# Bike_Gps_v1.net
KiCad netlist of a schematic drawn in Altium Designer
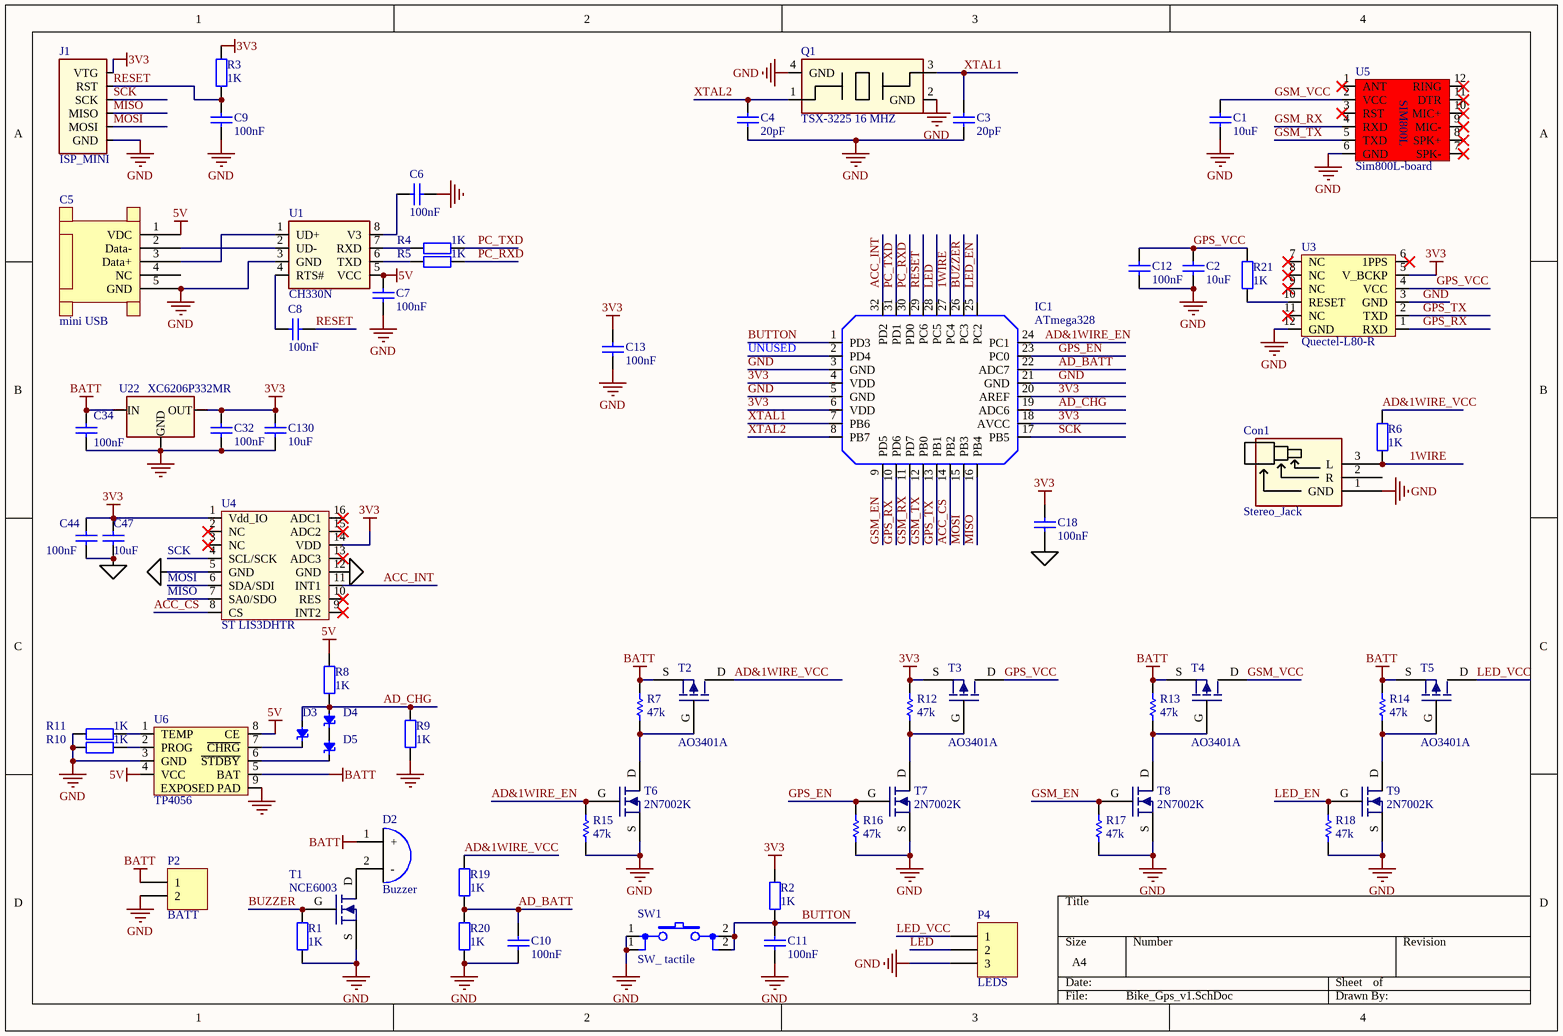
[diagram p0: Bike_Gps_v1.SchDoc]

(export (version "E")
  (design (tool "Eeschema 10.0.6"))
  (components
    (comp (ref "C1")
      (value "10uF")
      (footprint "FP_1206_CAP_085")
      (description "Capacitor ceramic X7R")
      (libsource (lib "Capacitor") (part "Cap"))
    )
    (comp (ref "C2")
      (value "10uF")
      (footprint "FP_1206_CAP_085")
      (description "Capacitor ceramic X7R")
      (libsource (lib "Capacitor") (part "Cap"))
    )
    (comp (ref "C3")
      (value "20pF")
      (footprint "FP_0603_CAP_080")
      (description "Capacitor")
      (fields (field (name "PART NUMBER") "20pF_0603_50V_NP0_5percent"))
      (libsource (lib "Miscellaneous Devices") (part "Cap"))
    )
    (comp (ref "C4")
      (value "20pF")
      (footprint "FP_0603_CAP_080")
      (description "Capacitor")
      (fields (field (name "PART NUMBER") "20pF_0603_50V_NP0_5percent"))
      (libsource (lib "Miscellaneous Devices") (part "Cap"))
    )
    (comp (ref "C5")
      (value "mini USB")
      (footprint "USB/SM0.8-6H5")
      (libsource (lib "mini USB") (part "mini USB"))
    )
    (comp (ref "C6")
      (value "100nF")
      (footprint "FP_0603_CAP_080")
      (description "Capacitor")
      (fields (field (name "PART NUMBER") "100nF_0603_50V_X7R_10percent"))
      (libsource (lib "Miscellaneous Devices") (part "Cap"))
    )
    (comp (ref "C7")
      (value "100nF")
      (footprint "FP_0603_CAP_080")
      (description "Capacitor")
      (fields (field (name "PART NUMBER") "100nF_0603_50V_X7R_10percent"))
      (libsource (lib "Miscellaneous Devices") (part "Cap"))
    )
    (comp (ref "C8")
      (value "100nF")
      (footprint "FP_0603_CAP_080")
      (description "Capacitor")
      (fields (field (name "PART NUMBER") "100nF_0603_50V_X7R_10percent"))
      (libsource (lib "Miscellaneous Devices") (part "Cap"))
    )
    (comp (ref "C9")
      (value "100nF")
      (footprint "FP_0603_CAP_080")
      (description "Capacitor")
      (fields (field (name "PART NUMBER") "100nF_0603_50V_X7R_10percent"))
      (libsource (lib "Miscellaneous Devices") (part "Cap"))
    )
    (comp (ref "C10")
      (value "100nF")
      (footprint "FP_0603_CAP_080")
      (description "Capacitor")
      (fields (field (name "PART NUMBER") "100nF_0603_50V_X7R_10percent"))
      (libsource (lib "Miscellaneous Devices") (part "Cap"))
    )
    (comp (ref "C11")
      (value "100nF")
      (footprint "FP_0603_CAP_080")
      (description "Capacitor")
      (fields (field (name "PART NUMBER") "100nF_0603_50V_X7R_10percent"))
      (libsource (lib "Miscellaneous Devices") (part "Cap"))
    )
    (comp (ref "C12")
      (value "100nF")
      (footprint "FP_0603_CAP_080")
      (description "Capacitor")
      (fields (field (name "PART NUMBER") "100nF_0603_50V_X7R_10percent"))
      (libsource (lib "Miscellaneous Devices") (part "Cap"))
    )
    (comp (ref "C13")
      (value "100nF")
      (footprint "FP_0603_CAP_080")
      (description "Capacitor")
      (fields (field (name "PART NUMBER") "100nF_0603_50V_X7R_10percent"))
      (libsource (lib "Miscellaneous Devices") (part "Cap"))
    )
    (comp (ref "C18")
      (value "100nF")
      (footprint "FP_0603_CAP_080")
      (description "Capacitor")
      (fields (field (name "PART NUMBER") "100nF_0603_50V_X7R_10percent"))
      (libsource (lib "Miscellaneous Devices") (part "Cap"))
    )
    (comp (ref "C32")
      (value "100nF")
      (footprint "FP_0603_CAP_080")
      (description "Capacitor")
      (fields (field (name "PART NUMBER") "100nF_0603_50V_X7R_10percent"))
      (libsource (lib "Miscellaneous Devices") (part "Cap"))
    )
    (comp (ref "C34")
      (value "100nF")
      (footprint "FP_0603_CAP_080")
      (description "Capacitor")
      (fields (field (name "PART NUMBER") "100nF_0603_50V_X7R_10percent"))
      (libsource (lib "Miscellaneous Devices") (part "Cap"))
    )
    (comp (ref "C44")
      (value "100nF")
      (footprint "FP_0603_CAP_080")
      (description "Capacitor")
      (fields (field (name "PART NUMBER") "100nF_0603_50V_X7R_10percent"))
      (libsource (lib "Capacitor") (part "CAP"))
    )
    (comp (ref "C47")
      (value "10uF")
      (footprint "FP_0805_CAP_085")
      (description "Capacitor")
      (fields (field (name "PART NUMBER") "10uF_0805_10V_X5R_10percent"))
      (libsource (lib "Capacitor") (part "CAP"))
    )
    (comp (ref "C130")
      (value "10uF")
      (footprint "FP_0805_CAP_085")
      (description "Capacitor")
      (fields (field (name "PART NUMBER") "10uF_0805_10V_X5R_10percent"))
      (libsource (lib "Capacitor") (part "CAP"))
    )
    (comp (ref "Con1")
      (value "Stereo_Jack")
      (footprint "STEREO_JACK")
      (libsource (lib "Connector") (part "Stereo_Jack"))
    )
    (comp (ref "D2") (value "Buzzer") (footprint "Buzzer_MBS12XXX") (libsource (lib "Other") (part "Buzzer")))
    (comp (ref "D3")
      (value "5.6V Zener")
      (footprint "FP_SOD323")
      (description "5.6V ±5% 300mW 1uA @ 2.5V SOD-323 Zener Diodes RoHS")
      (fields (field (name "PART NUMBER") "MM3Z5V6"))
      (libsource (lib "Diode") (part "5.6V Zener"))
    )
    (comp (ref "D4")
      (value "5.6V Zener")
      (footprint "FP_SOD323")
      (description "5.6V ±5% 300mW 1uA @ 2.5V SOD-323 Zener Diodes RoHS")
      (fields (field (name "PART NUMBER") "MM3Z5V6"))
      (libsource (lib "Diode") (part "5.6V Zener"))
    )
    (comp (ref "D5")
      (value "5.6V Zener")
      (footprint "FP_SOD323")
      (description "5.6V ±5% 300mW 1uA @ 2.5V SOD-323 Zener Diodes RoHS")
      (fields (field (name "PART NUMBER") "MM3Z5V6"))
      (libsource (lib "Diode") (part "5.6V Zener"))
    )
    (comp (ref "IC1") (value "ATmega328") (footprint "TQFP32_N") (libsource (lib "uC") (part "ATmega328")))
    (comp (ref "J1")
      (value "ISP_MINI")
      (footprint "AVR_ISP_MINI")
      (libsource (lib "Connector") (part "ISP_MINI"))
    )
    (comp (ref "P2")
      (value "BATT")
      (footprint "HEADER_2.54MM_M_1x2")
      (description "Header, 2-Pin")
      (libsource (lib "Header") (part "Header 1X2"))
    )
    (comp (ref "P4")
      (value "LEDS")
      (footprint "HEADER_2.54MM_M_1x3")
      (description "Header, 3-Pin")
      (fields (field (name "PUBLISHER") "Altium Limited"))
      (libsource (lib "Header") (part "Header 1X3"))
    )
    (comp (ref "Q1")
      (value "TSX-3225 16 MHZ")
      (footprint "FP_Cristal-3225")
      (description "CRYSTAL, TSX-3225, 16 MHZ, 9 PF")
      (libsource (lib "Quartz") (part "TSX-3225 25 MHZ"))
    )
    (comp (ref "R1")
      (value "1K")
      (footprint "FP_0603_RES")
      (description "Resistor")
      (fields (field (name "PART NUMBER") "1k_0603_1percent"))
      (libsource (lib "") (part "RES_2"))
    )
    (comp (ref "R2")
      (value "1K")
      (footprint "FP_0603_RES")
      (description "Resistor")
      (fields (field (name "PART NUMBER") "1k_0603_1percent"))
      (libsource (lib "") (part "RES_2"))
    )
    (comp (ref "R3")
      (value "1K")
      (footprint "FP_0603_RES")
      (description "Resistor")
      (fields (field (name "PART NUMBER") "1k_0603_1percent"))
      (libsource (lib "Resistor") (part "RES"))
    )
    (comp (ref "R4")
      (value "1K")
      (footprint "FP_0603_RES")
      (description "Resistor")
      (fields (field (name "PART NUMBER") "1k_0603_1percent"))
      (libsource (lib "") (part "RES_1"))
    )
    (comp (ref "R5")
      (value "1K")
      (footprint "FP_0603_RES")
      (description "Resistor")
      (fields (field (name "PART NUMBER") "1k_0603_1percent"))
      (libsource (lib "") (part "RES_1"))
    )
    (comp (ref "R6")
      (value "1K")
      (footprint "FP_0603_RES")
      (description "Resistor")
      (fields (field (name "PART NUMBER") "1k_0603_1percent"))
      (libsource (lib "") (part "RES_2"))
    )
    (comp (ref "R7")
      (value "47k")
      (footprint "FP_0603_RES")
      (description "Resistor")
      (fields (field (name "PART NUMBER") "47k_0603_1percent"))
      (libsource (lib "Miscellaneous Devices") (part "Res1"))
    )
    (comp (ref "R8")
      (value "1K")
      (footprint "FP_0603_RES")
      (description "Resistor")
      (fields (field (name "PART NUMBER") "1k_0603_1percent"))
      (libsource (lib "") (part "RES_2"))
    )
    (comp (ref "R9")
      (value "1K")
      (footprint "FP_0603_RES")
      (description "Resistor")
      (fields (field (name "PART NUMBER") "1k_0603_1percent"))
      (libsource (lib "") (part "RES_2"))
    )
    (comp (ref "R10")
      (value "1K")
      (footprint "FP_0603_RES")
      (description "Resistor")
      (fields (field (name "PART NUMBER") "1k_0603_1percent"))
      (libsource (lib "") (part "RES_1"))
    )
    (comp (ref "R11")
      (value "1K")
      (footprint "FP_0603_RES")
      (description "Resistor")
      (fields (field (name "PART NUMBER") "1k_0603_1percent"))
      (libsource (lib "") (part "RES_1"))
    )
    (comp (ref "R12")
      (value "47k")
      (footprint "FP_0603_RES")
      (description "Resistor")
      (fields (field (name "PART NUMBER") "47k_0603_1percent"))
      (libsource (lib "Miscellaneous Devices") (part "Res1"))
    )
    (comp (ref "R13")
      (value "47k")
      (footprint "FP_0603_RES")
      (description "Resistor")
      (fields (field (name "PART NUMBER") "47k_0603_1percent"))
      (libsource (lib "Miscellaneous Devices") (part "Res1"))
    )
    (comp (ref "R14")
      (value "47k")
      (footprint "FP_0603_RES")
      (description "Resistor")
      (fields (field (name "PART NUMBER") "47k_0603_1percent"))
      (libsource (lib "Miscellaneous Devices") (part "Res1"))
    )
    (comp (ref "R15")
      (value "47k")
      (footprint "FP_0603_RES")
      (description "Resistor")
      (fields (field (name "PART NUMBER") "47k_0603_1percent"))
      (libsource (lib "Miscellaneous Devices") (part "Res1"))
    )
    (comp (ref "R16")
      (value "47k")
      (footprint "FP_0603_RES")
      (description "Resistor")
      (fields (field (name "PART NUMBER") "47k_0603_1percent"))
      (libsource (lib "Miscellaneous Devices") (part "Res1"))
    )
    (comp (ref "R17")
      (value "47k")
      (footprint "FP_0603_RES")
      (description "Resistor")
      (fields (field (name "PART NUMBER") "47k_0603_1percent"))
      (libsource (lib "Miscellaneous Devices") (part "Res1"))
    )
    (comp (ref "R18")
      (value "47k")
      (footprint "FP_0603_RES")
      (description "Resistor")
      (fields (field (name "PART NUMBER") "47k_0603_1percent"))
      (libsource (lib "Miscellaneous Devices") (part "Res1"))
    )
    (comp (ref "R19")
      (value "1K")
      (footprint "FP_0603_RES")
      (description "Resistor")
      (fields (field (name "PART NUMBER") "1k_0603_1percent"))
      (libsource (lib "Resistor") (part "RES"))
    )
    (comp (ref "R20")
      (value "1K")
      (footprint "FP_0603_RES")
      (description "Resistor")
      (fields (field (name "PART NUMBER") "1k_0603_1percent"))
      (libsource (lib "Resistor") (part "RES"))
    )
    (comp (ref "R21")
      (value "1K")
      (footprint "FP_0603_RES")
      (description "Resistor")
      (fields (field (name "PART NUMBER") "1k_0603_1percent"))
      (libsource (lib "") (part "RES_2"))
    )
    (comp (ref "SW1")
      (value "SW_ tactile")
      (footprint "BUTTON_6X6")
      (libsource (lib "Switch") (part "SW_ tactile"))
    )
    (comp (ref "T1")
      (value "NCE6003")
      (footprint "FET_SOT23")
      (description "N Channel 60V 3A 2V @ 250uA 105 mΩ @ 3A,10V 1.7W SOT-23(SOT-23-3) MOSFET RoHS")
      (libsource (lib "FET") (part "NMOS"))
    )
    (comp (ref "T2")
      (value "AO3401A")
      (footprint "FET_SOT23")
      (description "P Channel 30V 4.1A 1.3V @ 250uA 65 mΩ @ 4.2A,10V 350mW SOT-23 MOSFET RoHS")
      (libsource (lib "FET") (part "PMOS"))
    )
    (comp (ref "T3")
      (value "AO3401A")
      (footprint "FET_SOT23")
      (description "P Channel 30V 4.1A 1.3V @ 250uA 65 mΩ @ 4.2A,10V 350mW SOT-23 MOSFET RoHS")
      (libsource (lib "FET") (part "PMOS"))
    )
    (comp (ref "T4")
      (value "AO3401A")
      (footprint "FET_SOT23")
      (description "P Channel 30V 4.1A 1.3V @ 250uA 65 mΩ @ 4.2A,10V 350mW SOT-23 MOSFET RoHS")
      (libsource (lib "FET") (part "PMOS"))
    )
    (comp (ref "T5")
      (value "AO3401A")
      (footprint "FET_SOT23")
      (description "P Channel 30V 4.1A 1.3V @ 250uA 65 mΩ @ 4.2A,10V 350mW SOT-23 MOSFET RoHS")
      (libsource (lib "FET") (part "PMOS"))
    )
    (comp (ref "T6")
      (value "2N7002K")
      (footprint "FET_SOT23")
      (description "N-Channel MOSFET")
      (libsource (lib "FET") (part "NMOS"))
    )
    (comp (ref "T7")
      (value "2N7002K")
      (footprint "FET_SOT23")
      (description "N-Channel MOSFET")
      (libsource (lib "FET") (part "NMOS"))
    )
    (comp (ref "T8")
      (value "2N7002K")
      (footprint "FET_SOT23")
      (description "N-Channel MOSFET")
      (libsource (lib "FET") (part "NMOS"))
    )
    (comp (ref "T9")
      (value "2N7002K")
      (footprint "FET_SOT23")
      (description "N-Channel MOSFET")
      (libsource (lib "FET") (part "NMOS"))
    )
    (comp (ref "U1")
      (value "CH330N")
      (footprint "DIGITAL_SOIC8")
      (description "Transceiver USB 2.0 2Mbps SOP-8_150mil USB ICs RoHS")
      (libsource (lib "Digital") (part "CH330N"))
    )
    (comp (ref "U3")
      (value "Quectel-L80-R")
      (footprint "Quectel-L80-R")
      (description "Quectel GPS module with embedded antenna")
      (libsource (lib "Modul") (part "Quectel-L80-R"))
    )
    (comp (ref "U4")
      (value "ST LIS3DHTR")
      (footprint "LGA 16 (3x3x1mm)")
      (description "ST LIS3DHTR 3 axis accelerometer")
      (fields (field (name "PART NUMBER") "LIS3DHTR"))
      (libsource (lib "Sensor") (part "ST LIS3DHTR"))
    )
    (comp (ref "U5")
      (value "Sim800L-board")
      (footprint "Sim800L-board")
      (description "Sim800L devboard with nano sim slot")
      (libsource (lib "Modul") (part "Sim800L-board"))
    )
    (comp (ref "U6")
      (value "TP4056")
      (footprint "Supply_SO8_PWP")
      (description "1A Li-on battery charger")
      (libsource (lib "Supply") (part "TP4056"))
    )
    (comp (ref "U22")
      (value "XC6206P332MR")
      (footprint "SUPPLY_SOT23")
      (description "Fixed 36V 5V 250mA SOT-23(SOT-23-3) Low Dropout Regulators(LDO) RoHS")
      (libsource (lib "Supply") (part "XC6206P332MR"))
    )
  )
  (nets
    (net (code "1") (name "/1WIRE") (class "Default")
      (node (ref "Con1") (pin "3") (pinfunction "L_3") (pintype "passive"))
      (node (ref "IC1") (pin "27") (pinfunction "PC4_27") (pintype "passive"))
      (node (ref "R6") (pin "2") (pinfunction "2_2") (pintype "passive"))
    )
    (net (code "2") (name "/ACC_CS") (class "Default")
      (node (ref "IC1") (pin "14") (pinfunction "PB2_14") (pintype "passive"))
      (node (ref "U4") (pin "8") (pinfunction "CS_8") (pintype "passive"))
    )
    (net (code "3") (name "/ACC_INT") (class "Default")
      (node (ref "IC1") (pin "32") (pinfunction "PD2_32") (pintype "passive"))
      (node (ref "U4") (pin "11") (pinfunction "INT1_11") (pintype "passive"))
    )
    (net (code "4") (name "/AD&1WIRE_EN") (class "Default")
      (node (ref "IC1") (pin "24") (pinfunction "PC1_24") (pintype "passive"))
      (node (ref "R15") (pin "2") (pinfunction "2_2") (pintype "passive"))
      (node (ref "T6") (pin "G") (pinfunction "G_G") (pintype "passive"))
    )
    (net (code "5") (name "/AD&1WIRE_VCC") (class "Default")
      (node (ref "R19") (pin "2") (pinfunction "2_2") (pintype "passive"))
      (node (ref "R6") (pin "1") (pinfunction "1_1") (pintype "passive"))
      (node (ref "T2") (pin "D") (pinfunction "D_D") (pintype "passive"))
    )
    (net (code "6") (name "/AD_BATT") (class "Default")
      (node (ref "C10") (pin "2") (pinfunction "2_2") (pintype "passive"))
      (node (ref "IC1") (pin "22") (pinfunction "ADC7_22") (pintype "passive"))
      (node (ref "R19") (pin "1") (pinfunction "1_1") (pintype "passive"))
      (node (ref "R20") (pin "2") (pinfunction "2_2") (pintype "passive"))
    )
    (net (code "7") (name "/AD_CHG") (class "Default")
      (node (ref "D3") (pin "A") (pinfunction "A_A") (pintype "passive"))
      (node (ref "D4") (pin "A") (pinfunction "A_A") (pintype "passive"))
      (node (ref "IC1") (pin "19") (pinfunction "ADC6_19") (pintype "passive"))
      (node (ref "R8") (pin "2") (pinfunction "2_2") (pintype "passive"))
      (node (ref "R9") (pin "1") (pinfunction "1_1") (pintype "passive"))
    )
    (net (code "8") (name "/BUTTON") (class "Default")
      (node (ref "C11") (pin "2") (pinfunction "2_2") (pintype "passive"))
      (node (ref "IC1") (pin "1") (pinfunction "PD3_1") (pintype "passive"))
      (node (ref "R2") (pin "2") (pinfunction "2_2") (pintype "passive"))
      (node (ref "SW1") (pin "2") (pinfunction "2_2") (pintype "passive"))
    )
    (net (code "9") (name "/BUZZER") (class "Default")
      (node (ref "IC1") (pin "26") (pinfunction "PC3_26") (pintype "passive"))
      (node (ref "R1") (pin "1") (pinfunction "1_1") (pintype "passive"))
      (node (ref "T1") (pin "G") (pinfunction "G_G") (pintype "passive"))
    )
    (net (code "10") (name "/GPS_EN") (class "Default")
      (node (ref "IC1") (pin "23") (pinfunction "PC0_23") (pintype "passive"))
      (node (ref "R16") (pin "2") (pinfunction "2_2") (pintype "passive"))
      (node (ref "T7") (pin "G") (pinfunction "G_G") (pintype "passive"))
    )
    (net (code "11") (name "/GPS_RX") (class "Default")
      (node (ref "IC1") (pin "10") (pinfunction "PD6_10") (pintype "passive"))
      (node (ref "U3") (pin "1") (pinfunction "RXD_1") (pintype "passive"))
    )
    (net (code "12") (name "/GPS_TX") (class "Default")
      (node (ref "IC1") (pin "13") (pinfunction "PB1_13") (pintype "passive"))
      (node (ref "U3") (pin "2") (pinfunction "TXD_2") (pintype "passive"))
    )
    (net (code "13") (name "/GPS_VCC") (class "Default")
      (node (ref "C12") (pin "2") (pinfunction "2_2") (pintype "passive"))
      (node (ref "C2") (pin "2") (pinfunction "2_2") (pintype "passive"))
      (node (ref "R21") (pin "1") (pinfunction "1_1") (pintype "passive"))
      (node (ref "T3") (pin "D") (pinfunction "D_D") (pintype "passive"))
      (node (ref "U3") (pin "4") (pinfunction "VCC_4") (pintype "passive"))
    )
    (net (code "14") (name "/GSM_EN") (class "Default")
      (node (ref "IC1") (pin "9") (pinfunction "PD5_9") (pintype "passive"))
      (node (ref "R17") (pin "2") (pinfunction "2_2") (pintype "passive"))
      (node (ref "T8") (pin "G") (pinfunction "G_G") (pintype "passive"))
    )
    (net (code "15") (name "/GSM_RX") (class "Default")
      (node (ref "IC1") (pin "11") (pinfunction "PD7_11") (pintype "passive"))
      (node (ref "U5") (pin "4") (pinfunction "RXD_4") (pintype "passive"))
    )
    (net (code "16") (name "/GSM_TX") (class "Default")
      (node (ref "IC1") (pin "12") (pinfunction "PB0_12") (pintype "passive"))
      (node (ref "U5") (pin "5") (pinfunction "TXD_5") (pintype "passive"))
    )
    (net (code "17") (name "/GSM_VCC") (class "Default")
      (node (ref "C1") (pin "1") (pinfunction "1_1") (pintype "passive"))
      (node (ref "T4") (pin "D") (pinfunction "D_D") (pintype "passive"))
      (node (ref "U5") (pin "2") (pinfunction "VCC_2") (pintype "passive"))
    )
    (net (code "18") (name "/LED") (class "Default")
      (node (ref "IC1") (pin "28") (pinfunction "PC5_28") (pintype "passive"))
      (node (ref "P4") (pin "2") (pinfunction "2_2") (pintype "passive"))
    )
    (net (code "19") (name "/LED_EN") (class "Default")
      (node (ref "IC1") (pin "25") (pinfunction "PC2_25") (pintype "passive"))
      (node (ref "R18") (pin "2") (pinfunction "2_2") (pintype "passive"))
      (node (ref "T9") (pin "G") (pinfunction "G_G") (pintype "passive"))
    )
    (net (code "20") (name "/LED_VCC") (class "Default")
      (node (ref "P4") (pin "1") (pinfunction "1_1") (pintype "passive"))
      (node (ref "T5") (pin "D") (pinfunction "D_D") (pintype "passive"))
    )
    (net (code "21") (name "/MISO") (class "Default")
      (node (ref "IC1") (pin "16") (pinfunction "PB4_16") (pintype "passive"))
      (node (ref "J1") (pin "4") (pinfunction "MISO_4") (pintype "passive"))
      (node (ref "U4") (pin "7") (pinfunction "SA0/SDO_7") (pintype "passive"))
    )
    (net (code "22") (name "/MOSI") (class "Default")
      (node (ref "IC1") (pin "15") (pinfunction "PB3_15") (pintype "passive"))
      (node (ref "J1") (pin "5") (pinfunction "MOSI_5") (pintype "passive"))
      (node (ref "U4") (pin "6") (pinfunction "SDA/SDI_6") (pintype "passive"))
    )
    (net (code "23") (name "/PC_RXD") (class "Default")
      (node (ref "IC1") (pin "30") (pinfunction "PD0_30") (pintype "passive"))
      (node (ref "R5") (pin "2") (pinfunction "2_2") (pintype "passive"))
    )
    (net (code "24") (name "/PC_TXD") (class "Default")
      (node (ref "IC1") (pin "31") (pinfunction "PD1_31") (pintype "passive"))
      (node (ref "R4") (pin "2") (pinfunction "2_2") (pintype "passive"))
    )
    (net (code "25") (name "/RESET") (class "Default")
      (node (ref "C8") (pin "1") (pinfunction "1_1") (pintype "passive"))
      (node (ref "C9") (pin "1") (pinfunction "1_1") (pintype "passive"))
      (node (ref "IC1") (pin "29") (pinfunction "PC6_29") (pintype "passive"))
      (node (ref "J1") (pin "2") (pinfunction "RST_2") (pintype "passive"))
      (node (ref "R3") (pin "1") (pinfunction "1_1") (pintype "passive"))
    )
    (net (code "26") (name "/SCK") (class "Default")
      (node (ref "IC1") (pin "17") (pinfunction "PB5_17") (pintype "passive"))
      (node (ref "J1") (pin "3") (pinfunction "SCK_3") (pintype "passive"))
      (node (ref "U4") (pin "4") (pinfunction "SCL/SCK_4") (pintype "passive"))
    )
    (net (code "27") (name "/UNUSED") (class "Default")
      (node (ref "IC1") (pin "2") (pinfunction "PD4_2") (pintype "passive"))
    )
    (net (code "28") (name "/XTAL1") (class "Default")
      (node (ref "C3") (pin "2") (pinfunction "2_2") (pintype "passive"))
      (node (ref "IC1") (pin "7") (pinfunction "PB6_7") (pintype "passive"))
      (node (ref "Q1") (pin "3") (pintype "passive"))
    )
    (net (code "29") (name "/XTAL2") (class "Default")
      (node (ref "C4") (pin "2") (pinfunction "2_2") (pintype "passive"))
      (node (ref "IC1") (pin "8") (pinfunction "PB7_8") (pintype "passive"))
      (node (ref "Q1") (pin "1") (pintype "passive"))
    )
    (net (code "30") (name "3V3") (class "Default")
      (node (ref "C13") (pin "2") (pinfunction "2_2") (pintype "passive"))
      (node (ref "C130") (pin "1") (pinfunction "1_1") (pintype "passive"))
      (node (ref "C18") (pin "2") (pinfunction "2_2") (pintype "passive"))
      (node (ref "C32") (pin "2") (pinfunction "2_2") (pintype "passive"))
      (node (ref "C44") (pin "2") (pinfunction "2_2") (pintype "passive"))
      (node (ref "C47") (pin "1") (pinfunction "1_1") (pintype "passive"))
      (node (ref "IC1") (pin "18") (pinfunction "AVCC_18") (pintype "passive"))
      (node (ref "IC1") (pin "20") (pinfunction "AREF_20") (pintype "passive"))
      (node (ref "IC1") (pin "4") (pinfunction "VDD_4") (pintype "passive"))
      (node (ref "IC1") (pin "6") (pinfunction "VDD_6") (pintype "passive"))
      (node (ref "J1") (pin "1") (pinfunction "VTG_1") (pintype "passive"))
      (node (ref "R12") (pin "2") (pinfunction "2_2") (pintype "passive"))
      (node (ref "R2") (pin "1") (pinfunction "1_1") (pintype "passive"))
      (node (ref "R3") (pin "2") (pinfunction "2_2") (pintype "passive"))
      (node (ref "T3") (pin "S") (pinfunction "S_S") (pintype "passive"))
      (node (ref "U22") (pin "VOUT") (pinfunction "OUT_VOUT") (pintype "power_in"))
      (node (ref "U3") (pin "5") (pinfunction "V_BCKP_5") (pintype "passive"))
      (node (ref "U4") (pin "1") (pinfunction "Vdd_IO_1") (pintype "passive"))
      (node (ref "U4") (pin "14") (pinfunction "VDD_14") (pintype "passive"))
    )
    (net (code "31") (name "5V") (class "Default")
      (node (ref "C5") (pin "1") (pinfunction "VDC_1") (pintype "passive"))
      (node (ref "C7") (pin "1") (pinfunction "1_1") (pintype "passive"))
      (node (ref "R8") (pin "1") (pinfunction "1_1") (pintype "passive"))
      (node (ref "U1") (pin "5") (pinfunction "VCC_5") (pintype "passive"))
      (node (ref "U6") (pin "4") (pinfunction "VCC_4") (pintype "passive"))
      (node (ref "U6") (pin "8") (pinfunction "CE_8") (pintype "passive"))
    )
    (net (code "32") (name "BATT") (class "Default")
      (node (ref "C34") (pin "2") (pinfunction "2_2") (pintype "passive"))
      (node (ref "D2") (pin "1") (pinfunction "+_1") (pintype "passive"))
      (node (ref "P2") (pin "1") (pinfunction "1_1") (pintype "passive"))
      (node (ref "R13") (pin "2") (pinfunction "2_2") (pintype "passive"))
      (node (ref "R14") (pin "2") (pinfunction "2_2") (pintype "passive"))
      (node (ref "R7") (pin "2") (pinfunction "2_2") (pintype "passive"))
      (node (ref "T2") (pin "S") (pinfunction "S_S") (pintype "passive"))
      (node (ref "T4") (pin "S") (pinfunction "S_S") (pintype "passive"))
      (node (ref "T5") (pin "S") (pinfunction "S_S") (pintype "passive"))
      (node (ref "U22") (pin "VIN") (pinfunction "IN_VIN") (pintype "power_in"))
      (node (ref "U6") (pin "5") (pinfunction "BAT_5") (pintype "passive"))
    )
    (net (code "33") (name "GND") (class "Default")
      (node (ref "C1") (pin "2") (pinfunction "2_2") (pintype "passive"))
      (node (ref "C10") (pin "1") (pinfunction "1_1") (pintype "passive"))
      (node (ref "C11") (pin "1") (pinfunction "1_1") (pintype "passive"))
      (node (ref "C12") (pin "1") (pinfunction "1_1") (pintype "passive"))
      (node (ref "C13") (pin "1") (pinfunction "1_1") (pintype "passive"))
      (node (ref "C130") (pin "2") (pinfunction "2_2") (pintype "passive"))
      (node (ref "C18") (pin "1") (pinfunction "1_1") (pintype "passive"))
      (node (ref "C2") (pin "1") (pinfunction "1_1") (pintype "passive"))
      (node (ref "C3") (pin "1") (pinfunction "1_1") (pintype "passive"))
      (node (ref "C32") (pin "1") (pinfunction "1_1") (pintype "passive"))
      (node (ref "C34") (pin "1") (pinfunction "1_1") (pintype "passive"))
      (node (ref "C4") (pin "1") (pinfunction "1_1") (pintype "passive"))
      (node (ref "C44") (pin "1") (pinfunction "1_1") (pintype "passive"))
      (node (ref "C47") (pin "2") (pinfunction "2_2") (pintype "passive"))
      (node (ref "C5") (pin "5") (pinfunction "GND_5") (pintype "passive"))
      (node (ref "C6") (pin "1") (pinfunction "1_1") (pintype "passive"))
      (node (ref "C7") (pin "2") (pinfunction "2_2") (pintype "passive"))
      (node (ref "C9") (pin "2") (pinfunction "2_2") (pintype "passive"))
      (node (ref "Con1") (pin "1") (pinfunction "GND_1") (pintype "passive"))
      (node (ref "IC1") (pin "21") (pinfunction "GND_21") (pintype "passive"))
      (node (ref "IC1") (pin "3") (pinfunction "GND_3") (pintype "passive"))
      (node (ref "IC1") (pin "5") (pinfunction "GND_5") (pintype "passive"))
      (node (ref "J1") (pin "6") (pinfunction "GND_6") (pintype "passive"))
      (node (ref "P2") (pin "2") (pinfunction "2_2") (pintype "passive"))
      (node (ref "P4") (pin "3") (pinfunction "3_3") (pintype "passive"))
      (node (ref "Q1") (pin "2") (pinfunction "GND_2") (pintype "passive"))
      (node (ref "Q1") (pin "4") (pinfunction "GND_4") (pintype "passive"))
      (node (ref "R1") (pin "2") (pinfunction "2_2") (pintype "passive"))
      (node (ref "R10") (pin "1") (pinfunction "1_1") (pintype "passive"))
      (node (ref "R11") (pin "1") (pinfunction "1_1") (pintype "passive"))
      (node (ref "R15") (pin "1") (pinfunction "1_1") (pintype "passive"))
      (node (ref "R16") (pin "1") (pinfunction "1_1") (pintype "passive"))
      (node (ref "R17") (pin "1") (pinfunction "1_1") (pintype "passive"))
      (node (ref "R18") (pin "1") (pinfunction "1_1") (pintype "passive"))
      (node (ref "R20") (pin "1") (pinfunction "1_1") (pintype "passive"))
      (node (ref "R9") (pin "2") (pinfunction "2_2") (pintype "passive"))
      (node (ref "SW1") (pin "1") (pinfunction "1_1") (pintype "passive"))
      (node (ref "T1") (pin "S") (pinfunction "S_S") (pintype "passive"))
      (node (ref "T6") (pin "S") (pinfunction "S_S") (pintype "passive"))
      (node (ref "T7") (pin "S") (pinfunction "S_S") (pintype "passive"))
      (node (ref "T8") (pin "S") (pinfunction "S_S") (pintype "passive"))
      (node (ref "T9") (pin "S") (pinfunction "S_S") (pintype "passive"))
      (node (ref "U1") (pin "3") (pinfunction "GND_3") (pintype "passive"))
      (node (ref "U22") (pin "GND") (pinfunction "GND_GND") (pintype "power_in"))
      (node (ref "U3") (pin "12") (pinfunction "GND_12") (pintype "passive"))
      (node (ref "U3") (pin "3") (pinfunction "GND_3") (pintype "passive"))
      (node (ref "U4") (pin "12") (pinfunction "GND_12") (pintype "passive"))
      (node (ref "U4") (pin "5") (pinfunction "GND_5") (pintype "passive"))
      (node (ref "U5") (pin "6") (pinfunction "GND_6") (pintype "passive"))
      (node (ref "U6") (pin "3") (pinfunction "GND_3") (pintype "passive"))
      (node (ref "U6") (pin "9") (pinfunction "EXPOSED_PAD_9") (pintype "passive"))
    )
    (net (code "34") (name "Net-(C5-Data+)") (class "Default")
      (node (ref "C5") (pin "3") (pinfunction "Data+_3") (pintype "passive"))
      (node (ref "U1") (pin "1") (pinfunction "UD+_1") (pintype "passive"))
    )
    (net (code "35") (name "Net-(C5-Data-)") (class "Default")
      (node (ref "C5") (pin "2") (pinfunction "Data-_2") (pintype "passive"))
      (node (ref "U1") (pin "2") (pinfunction "UD-_2") (pintype "passive"))
    )
    (net (code "36") (name "Net-(D2--)") (class "Default")
      (node (ref "D2") (pin "2") (pinfunction "-_2") (pintype "passive"))
      (node (ref "T1") (pin "D") (pinfunction "D_D") (pintype "passive"))
    )
    (net (code "37") (name "Net-(D4-PadK)") (class "Default")
      (node (ref "D4") (pin "K") (pinfunction "K_K") (pintype "passive"))
      (node (ref "D5") (pin "A") (pinfunction "A_A") (pintype "passive"))
    )
    (net (code "38") (name "Net-(R7-Pad1)") (class "Default")
      (node (ref "R7") (pin "1") (pinfunction "1_1") (pintype "passive"))
      (node (ref "T2") (pin "G") (pinfunction "G_G") (pintype "passive"))
      (node (ref "T6") (pin "D") (pinfunction "D_D") (pintype "passive"))
    )
    (net (code "39") (name "Net-(R12-Pad1)") (class "Default")
      (node (ref "R12") (pin "1") (pinfunction "1_1") (pintype "passive"))
      (node (ref "T3") (pin "G") (pinfunction "G_G") (pintype "passive"))
      (node (ref "T7") (pin "D") (pinfunction "D_D") (pintype "passive"))
    )
    (net (code "40") (name "Net-(R13-Pad1)") (class "Default")
      (node (ref "R13") (pin "1") (pinfunction "1_1") (pintype "passive"))
      (node (ref "T4") (pin "G") (pinfunction "G_G") (pintype "passive"))
      (node (ref "T8") (pin "D") (pinfunction "D_D") (pintype "passive"))
    )
    (net (code "41") (name "Net-(R14-Pad1)") (class "Default")
      (node (ref "R14") (pin "1") (pinfunction "1_1") (pintype "passive"))
      (node (ref "T5") (pin "G") (pinfunction "G_G") (pintype "passive"))
      (node (ref "T9") (pin "D") (pinfunction "D_D") (pintype "passive"))
    )
    (net (code "42") (name "Net-(U1-RTS#)") (class "Default")
      (node (ref "C8") (pin "2") (pinfunction "2_2") (pintype "passive"))
      (node (ref "U1") (pin "4") (pinfunction "RTS#_4") (pintype "passive"))
    )
    (net (code "43") (name "Net-(U1-RXD)") (class "Default")
      (node (ref "R4") (pin "1") (pinfunction "1_1") (pintype "passive"))
      (node (ref "U1") (pin "7") (pinfunction "RXD_7") (pintype "passive"))
    )
    (net (code "44") (name "Net-(U1-TXD)") (class "Default")
      (node (ref "R5") (pin "1") (pinfunction "1_1") (pintype "passive"))
      (node (ref "U1") (pin "6") (pinfunction "TXD_6") (pintype "passive"))
    )
    (net (code "45") (name "Net-(U1-V3)") (class "Default")
      (node (ref "C6") (pin "2") (pinfunction "2_2") (pintype "passive"))
      (node (ref "U1") (pin "8") (pinfunction "V3_8") (pintype "passive"))
    )
    (net (code "46") (name "Net-(U3-RESET)") (class "Default")
      (node (ref "R21") (pin "2") (pinfunction "2_2") (pintype "passive"))
      (node (ref "U3") (pin "10") (pinfunction "RESET_10") (pintype "passive"))
    )
    (net (code "47") (name "Net-(U6-PROG)") (class "Default")
      (node (ref "R10") (pin "2") (pinfunction "2_2") (pintype "passive"))
      (node (ref "U6") (pin "2") (pinfunction "PROG_2") (pintype "passive"))
    )
    (net (code "48") (name "Net-(U6-TEMP)") (class "Default")
      (node (ref "R11") (pin "2") (pinfunction "2_2") (pintype "passive"))
      (node (ref "U6") (pin "1") (pinfunction "TEMP_1") (pintype "passive"))
    )
    (net (code "49") (name "Net-(U6-~{CHRG})") (class "Default")
      (node (ref "D3") (pin "K") (pinfunction "K_K") (pintype "passive"))
      (node (ref "U6") (pin "7") (pinfunction "~{CHRG}_7") (pintype "passive"))
    )
    (net (code "50") (name "Net-(U6-~{STDBY})") (class "Default")
      (node (ref "D5") (pin "K") (pinfunction "K_K") (pintype "passive"))
      (node (ref "U6") (pin "6") (pinfunction "~{STDBY}_6") (pintype "passive"))
    )
    (net (code "51") (name "unconnected-(C5-NC-Pad4)") (class "Default")
      (node (ref "C5") (pin "4") (pinfunction "NC_4") (pintype "passive"))
    )
    (net (code "52") (name "unconnected-(Con1-R-Pad2)") (class "Default")
      (node (ref "Con1") (pin "2") (pinfunction "R_2") (pintype "passive"))
    )
    (net (code "53") (name "unconnected-(U3-1PPS-Pad6)") (class "Default")
      (node (ref "U3") (pin "6") (pinfunction "1PPS_6") (pintype "passive+no_connect"))
    )
    (net (code "54") (name "unconnected-(U3-NC-Pad7)") (class "Default")
      (node (ref "U3") (pin "7") (pinfunction "NC_7") (pintype "passive+no_connect"))
    )
    (net (code "55") (name "unconnected-(U3-NC-Pad8)") (class "Default")
      (node (ref "U3") (pin "8") (pinfunction "NC_8") (pintype "passive+no_connect"))
    )
    (net (code "56") (name "unconnected-(U3-NC-Pad9)") (class "Default")
      (node (ref "U3") (pin "9") (pinfunction "NC_9") (pintype "passive+no_connect"))
    )
    (net (code "57") (name "unconnected-(U3-NC-Pad11)") (class "Default")
      (node (ref "U3") (pin "11") (pinfunction "NC_11") (pintype "passive+no_connect"))
    )
    (net (code "58") (name "unconnected-(U4-ADC1-Pad16)") (class "Default")
      (node (ref "U4") (pin "16") (pinfunction "ADC1_16") (pintype "passive+no_connect"))
    )
    (net (code "59") (name "unconnected-(U4-ADC2-Pad15)") (class "Default")
      (node (ref "U4") (pin "15") (pinfunction "ADC2_15") (pintype "passive+no_connect"))
    )
    (net (code "60") (name "unconnected-(U4-ADC3-Pad13)") (class "Default")
      (node (ref "U4") (pin "13") (pinfunction "ADC3_13") (pintype "passive+no_connect"))
    )
    (net (code "61") (name "unconnected-(U4-INT2-Pad9)") (class "Default")
      (node (ref "U4") (pin "9") (pinfunction "INT2_9") (pintype "passive+no_connect"))
    )
    (net (code "62") (name "unconnected-(U4-NC-Pad2)") (class "Default")
      (node (ref "U4") (pin "2") (pinfunction "NC_2") (pintype "passive+no_connect"))
    )
    (net (code "63") (name "unconnected-(U4-NC-Pad3)") (class "Default")
      (node (ref "U4") (pin "3") (pinfunction "NC_3") (pintype "passive+no_connect"))
    )
    (net (code "64") (name "unconnected-(U4-RES-Pad10)") (class "Default")
      (node (ref "U4") (pin "10") (pinfunction "RES_10") (pintype "passive+no_connect"))
    )
    (net (code "65") (name "unconnected-(U5-ANT-Pad1)") (class "Default")
      (node (ref "U5") (pin "1") (pinfunction "ANT_1") (pintype "passive+no_connect"))
    )
    (net (code "66") (name "unconnected-(U5-DTR-Pad11)") (class "Default")
      (node (ref "U5") (pin "11") (pinfunction "DTR_11") (pintype "passive+no_connect"))
    )
    (net (code "67") (name "unconnected-(U5-MIC+-Pad10)") (class "Default")
      (node (ref "U5") (pin "10") (pinfunction "MIC+_10") (pintype "passive+no_connect"))
    )
    (net (code "68") (name "unconnected-(U5-MIC--Pad9)") (class "Default")
      (node (ref "U5") (pin "9") (pinfunction "MIC-_9") (pintype "passive+no_connect"))
    )
    (net (code "69") (name "unconnected-(U5-RING-Pad12)") (class "Default")
      (node (ref "U5") (pin "12") (pinfunction "RING_12") (pintype "passive+no_connect"))
    )
    (net (code "70") (name "unconnected-(U5-RST-Pad3)") (class "Default")
      (node (ref "U5") (pin "3") (pinfunction "RST_3") (pintype "passive+no_connect"))
    )
    (net (code "71") (name "unconnected-(U5-SPK+-Pad8)") (class "Default")
      (node (ref "U5") (pin "8") (pinfunction "SPK+_8") (pintype "passive+no_connect"))
    )
    (net (code "72") (name "unconnected-(U5-SPK--Pad7)") (class "Default")
      (node (ref "U5") (pin "7") (pinfunction "SPK-_7") (pintype "passive+no_connect"))
    )
  )
)
